# Connectors.net
KiCad netlist of a schematic drawn in Altium Designer
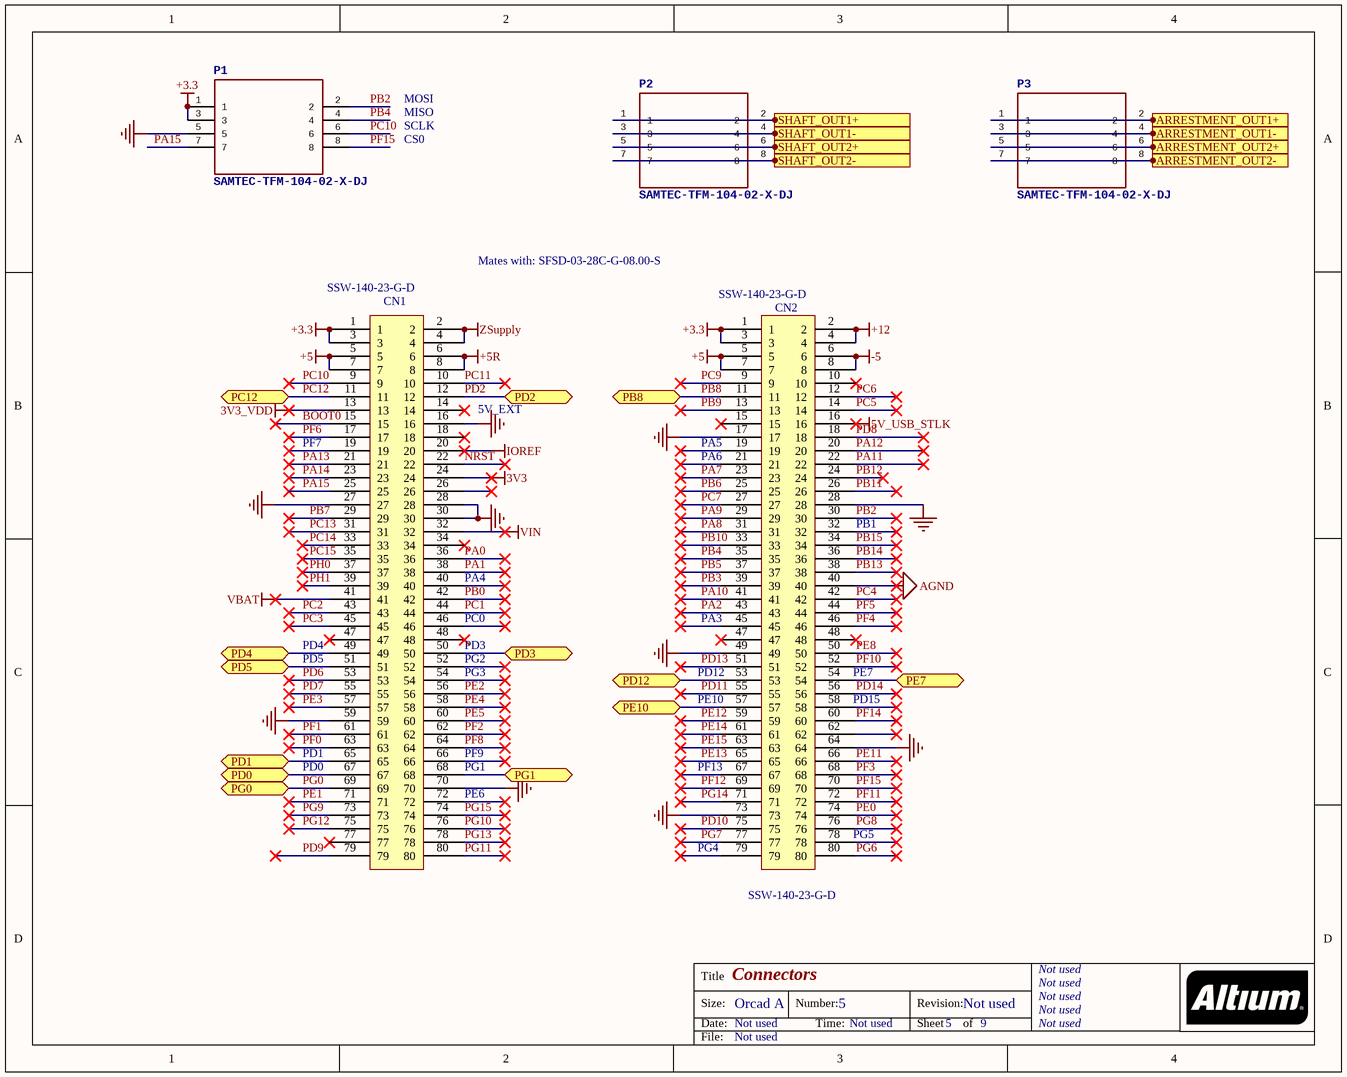
[diagram p0: Connectors.SchDoc]

(export (version "E")
  (design (tool "Eeschema 10.0.6"))
  (components
    (comp (ref "CN1")
      (value "SSW-140-23-G-D")
      (footprint "SSW-140-23-G-D")
      (description "80 Position Receptacle Connector Through Hole")
      (fields (field (name "SUPPLIER PART NUMBER 1") "SSW-140-23-G-D") (field (name "MANUFACTURER") "Samtec"))
      (libsource (lib "ZLS_Schematic_lib") (part "SSW-140-23-G-D"))
    )
    (comp (ref "CN2")
      (value "SSW-140-23-G-D")
      (footprint "SSW-140-23-G-D")
      (description "80 Position Receptacle Connector Through Hole")
      (fields (field (name "SUPPLIER PART NUMBER 1") "SSW-140-23-G-D") (field (name "MANUFACTURER") "Samtec"))
      (libsource (lib "ZLS_Schematic_lib") (part "SSW-140-23-G-D"))
    )
    (comp (ref "P1")
      (value "SAMTEC-TFM-104-02-X-DJ")
      (footprint "SAMTEC-TFM-104-02-X-D")
      (libsource (lib "SAMTEC-TFM-104-02-X-D") (part "SAMTEC-TFM-104-02-X-DJ"))
    )
    (comp (ref "P2")
      (value "SAMTEC-TFM-104-02-X-DJ")
      (footprint "SAMTEC-TFM-104-02-X-D")
      (libsource (lib "SAMTEC-TFM-104-02-X-D") (part "SAMTEC-TFM-104-02-X-DJ"))
    )
    (comp (ref "P3")
      (value "SAMTEC-TFM-104-02-X-DJ")
      (footprint "SAMTEC-TFM-104-02-X-D")
      (libsource (lib "SAMTEC-TFM-104-02-X-D") (part "SAMTEC-TFM-104-02-X-DJ"))
    )
  )
  (nets
    (net (code "1") (name "+3.3") (class "Default")
      (node (ref "CN1") (pin "1") (pinfunction "1_1") (pintype "passive"))
      (node (ref "CN1") (pin "3") (pinfunction "3_3") (pintype "passive"))
      (node (ref "CN2") (pin "1") (pinfunction "1_1") (pintype "passive"))
      (node (ref "CN2") (pin "3") (pinfunction "3_3") (pintype "passive"))
      (node (ref "P1") (pin "1") (pinfunction "1_1") (pintype "passive"))
      (node (ref "P1") (pin "3") (pinfunction "3_3") (pintype "passive"))
    )
    (net (code "2") (name "+5") (class "Default")
      (node (ref "CN1") (pin "5") (pinfunction "5_5") (pintype "passive"))
      (node (ref "CN1") (pin "7") (pinfunction "7_7") (pintype "passive"))
      (node (ref "CN2") (pin "5") (pinfunction "5_5") (pintype "passive"))
      (node (ref "CN2") (pin "7") (pinfunction "7_7") (pintype "passive"))
    )
    (net (code "3") (name "+5R") (class "Default")
      (node (ref "CN1") (pin "6") (pinfunction "6_6") (pintype "passive"))
      (node (ref "CN1") (pin "8") (pinfunction "8_8") (pintype "passive"))
    )
    (net (code "4") (name "+12") (class "Default")
      (node (ref "CN2") (pin "2") (pinfunction "2_2") (pintype "passive"))
      (node (ref "CN2") (pin "4") (pinfunction "4_4") (pintype "passive"))
    )
    (net (code "5") (name "-5") (class "Default")
      (node (ref "CN2") (pin "6") (pinfunction "6_6") (pintype "passive"))
      (node (ref "CN2") (pin "8") (pinfunction "8_8") (pintype "passive"))
    )
    (net (code "6") (name "/ARRESTMENT_OUT1+") (class "Default")
      (node (ref "P3") (pin "1") (pinfunction "1_1") (pintype "passive"))
      (node (ref "P3") (pin "2") (pinfunction "2_2") (pintype "passive"))
    )
    (net (code "7") (name "/ARRESTMENT_OUT1-") (class "Default")
      (node (ref "P3") (pin "3") (pinfunction "3_3") (pintype "passive"))
      (node (ref "P3") (pin "4") (pinfunction "4_4") (pintype "passive"))
    )
    (net (code "8") (name "/ARRESTMENT_OUT2+") (class "Default")
      (node (ref "P3") (pin "5") (pinfunction "5_5") (pintype "passive"))
      (node (ref "P3") (pin "6") (pinfunction "6_6") (pintype "passive"))
    )
    (net (code "9") (name "/ARRESTMENT_OUT2-") (class "Default")
      (node (ref "P3") (pin "7") (pinfunction "7_7") (pintype "passive"))
      (node (ref "P3") (pin "8") (pinfunction "8_8") (pintype "passive"))
    )
    (net (code "10") (name "/BOOT0") (class "Default")
      (node (ref "CN1") (pin "15") (pinfunction "15_15") (pintype "passive+no_connect"))
    )
    (net (code "11") (name "/NRST") (class "Default")
      (node (ref "CN1") (pin "22") (pinfunction "22_22") (pintype "passive+no_connect"))
    )
    (net (code "12") (name "/PA0") (class "Default")
      (node (ref "CN1") (pin "36") (pinfunction "36_36") (pintype "passive+no_connect"))
    )
    (net (code "13") (name "/PA1") (class "Default")
      (node (ref "CN1") (pin "38") (pinfunction "38_38") (pintype "passive+no_connect"))
    )
    (net (code "14") (name "/PA2") (class "Default")
      (node (ref "CN2") (pin "43") (pinfunction "43_43") (pintype "passive+no_connect"))
    )
    (net (code "15") (name "/PA7") (class "Default")
      (node (ref "CN2") (pin "23") (pinfunction "23_23") (pintype "passive+no_connect"))
    )
    (net (code "16") (name "/PA8") (class "Default")
      (node (ref "CN2") (pin "31") (pinfunction "31_31") (pintype "passive+no_connect"))
    )
    (net (code "17") (name "/PA9") (class "Default")
      (node (ref "CN2") (pin "29") (pinfunction "29_29") (pintype "passive+no_connect"))
    )
    (net (code "18") (name "/PA10") (class "Default")
      (node (ref "CN2") (pin "41") (pinfunction "41_41") (pintype "passive+no_connect"))
    )
    (net (code "19") (name "/PA11") (class "Default")
      (node (ref "CN2") (pin "22") (pinfunction "22_22") (pintype "passive+no_connect"))
    )
    (net (code "20") (name "/PA12") (class "Default")
      (node (ref "CN2") (pin "20") (pinfunction "20_20") (pintype "passive+no_connect"))
    )
    (net (code "21") (name "/PA13") (class "Default")
      (node (ref "CN1") (pin "21") (pinfunction "21_21") (pintype "passive+no_connect"))
    )
    (net (code "22") (name "/PA14") (class "Default")
      (node (ref "CN1") (pin "23") (pinfunction "23_23") (pintype "passive+no_connect"))
    )
    (net (code "23") (name "/PA15") (class "Default")
      (node (ref "CN1") (pin "25") (pinfunction "25_25") (pintype "passive"))
      (node (ref "P1") (pin "7") (pinfunction "7_7") (pintype "passive"))
    )
    (net (code "24") (name "/PB0") (class "Default")
      (node (ref "CN1") (pin "42") (pinfunction "42_42") (pintype "passive+no_connect"))
    )
    (net (code "25") (name "/PB2") (class "Default")
      (node (ref "CN2") (pin "30") (pinfunction "30_30") (pintype "passive"))
      (node (ref "P1") (pin "2") (pinfunction "2_2") (pintype "passive"))
    )
    (net (code "26") (name "/PB3") (class "Default")
      (node (ref "CN2") (pin "39") (pinfunction "39_39") (pintype "passive+no_connect"))
    )
    (net (code "27") (name "/PB4") (class "Default")
      (node (ref "CN2") (pin "35") (pinfunction "35_35") (pintype "passive"))
      (node (ref "P1") (pin "4") (pinfunction "4_4") (pintype "passive"))
    )
    (net (code "28") (name "/PB5") (class "Default")
      (node (ref "CN2") (pin "37") (pinfunction "37_37") (pintype "passive+no_connect"))
    )
    (net (code "29") (name "/PB6") (class "Default")
      (node (ref "CN2") (pin "25") (pinfunction "25_25") (pintype "passive+no_connect"))
    )
    (net (code "30") (name "/PB7") (class "Default")
      (node (ref "CN1") (pin "29") (pinfunction "29_29") (pintype "passive+no_connect"))
    )
    (net (code "31") (name "/PB8") (class "Default")
      (node (ref "CN2") (pin "11") (pinfunction "11_11") (pintype "passive"))
    )
    (net (code "32") (name "/PB9") (class "Default")
      (node (ref "CN2") (pin "13") (pinfunction "13_13") (pintype "passive+no_connect"))
    )
    (net (code "33") (name "/PB10") (class "Default")
      (node (ref "CN2") (pin "33") (pinfunction "33_33") (pintype "passive+no_connect"))
    )
    (net (code "34") (name "/PB11") (class "Default")
      (node (ref "CN2") (pin "26") (pinfunction "26_26") (pintype "passive+no_connect"))
    )
    (net (code "35") (name "/PB12") (class "Default")
      (node (ref "CN2") (pin "24") (pinfunction "24_24") (pintype "passive+no_connect"))
    )
    (net (code "36") (name "/PB13") (class "Default")
      (node (ref "CN2") (pin "38") (pinfunction "38_38") (pintype "passive+no_connect"))
    )
    (net (code "37") (name "/PB14") (class "Default")
      (node (ref "CN2") (pin "36") (pinfunction "36_36") (pintype "passive+no_connect"))
    )
    (net (code "38") (name "/PB15") (class "Default")
      (node (ref "CN2") (pin "34") (pinfunction "34_34") (pintype "passive+no_connect"))
    )
    (net (code "39") (name "/PC1") (class "Default")
      (node (ref "CN1") (pin "44") (pinfunction "44_44") (pintype "passive+no_connect"))
    )
    (net (code "40") (name "/PC2") (class "Default")
      (node (ref "CN1") (pin "43") (pinfunction "43_43") (pintype "passive+no_connect"))
    )
    (net (code "41") (name "/PC3") (class "Default")
      (node (ref "CN1") (pin "45") (pinfunction "45_45") (pintype "passive+no_connect"))
    )
    (net (code "42") (name "/PC4") (class "Default")
      (node (ref "CN2") (pin "42") (pinfunction "42_42") (pintype "passive+no_connect"))
    )
    (net (code "43") (name "/PC5") (class "Default")
      (node (ref "CN2") (pin "14") (pinfunction "14_14") (pintype "passive+no_connect"))
    )
    (net (code "44") (name "/PC6") (class "Default")
      (node (ref "CN2") (pin "12") (pinfunction "12_12") (pintype "passive+no_connect"))
    )
    (net (code "45") (name "/PC7") (class "Default")
      (node (ref "CN2") (pin "27") (pinfunction "27_27") (pintype "passive+no_connect"))
    )
    (net (code "46") (name "/PC9") (class "Default")
      (node (ref "CN2") (pin "9") (pinfunction "9_9") (pintype "passive+no_connect"))
    )
    (net (code "47") (name "/PC10") (class "Default")
      (node (ref "CN1") (pin "9") (pinfunction "9_9") (pintype "passive"))
      (node (ref "P1") (pin "6") (pinfunction "6_6") (pintype "passive"))
    )
    (net (code "48") (name "/PC11") (class "Default")
      (node (ref "CN1") (pin "10") (pinfunction "10_10") (pintype "passive+no_connect"))
    )
    (net (code "49") (name "/PC12") (class "Default")
      (node (ref "CN1") (pin "11") (pinfunction "11_11") (pintype "passive"))
    )
    (net (code "50") (name "/PC13") (class "Default")
      (node (ref "CN1") (pin "31") (pinfunction "31_31") (pintype "passive+no_connect"))
    )
    (net (code "51") (name "/PC14") (class "Default")
      (node (ref "CN1") (pin "33") (pinfunction "33_33") (pintype "passive+no_connect"))
    )
    (net (code "52") (name "/PC15") (class "Default")
      (node (ref "CN1") (pin "35") (pinfunction "35_35") (pintype "passive+no_connect"))
    )
    (net (code "53") (name "/PD0") (class "Default")
      (node (ref "CN1") (pin "67") (pinfunction "67_67") (pintype "passive"))
    )
    (net (code "54") (name "/PD1") (class "Default")
      (node (ref "CN1") (pin "65") (pinfunction "65_65") (pintype "passive"))
    )
    (net (code "55") (name "/PD2") (class "Default")
      (node (ref "CN1") (pin "12") (pinfunction "12_12") (pintype "passive"))
    )
    (net (code "56") (name "/PD3") (class "Default")
      (node (ref "CN1") (pin "50") (pinfunction "50_50") (pintype "passive"))
    )
    (net (code "57") (name "/PD4") (class "Default")
      (node (ref "CN1") (pin "49") (pinfunction "49_49") (pintype "passive"))
    )
    (net (code "58") (name "/PD5") (class "Default")
      (node (ref "CN1") (pin "51") (pinfunction "51_51") (pintype "passive"))
    )
    (net (code "59") (name "/PD6") (class "Default")
      (node (ref "CN1") (pin "53") (pinfunction "53_53") (pintype "passive+no_connect"))
    )
    (net (code "60") (name "/PD7") (class "Default")
      (node (ref "CN1") (pin "55") (pinfunction "55_55") (pintype "passive+no_connect"))
    )
    (net (code "61") (name "/PD8") (class "Default")
      (node (ref "CN2") (pin "18") (pinfunction "18_18") (pintype "passive+no_connect"))
    )
    (net (code "62") (name "/PD9") (class "Default")
      (node (ref "CN1") (pin "79") (pinfunction "79_79") (pintype "passive+no_connect"))
    )
    (net (code "63") (name "/PD10") (class "Default")
      (node (ref "CN2") (pin "75") (pinfunction "75_75") (pintype "passive+no_connect"))
    )
    (net (code "64") (name "/PD11") (class "Default")
      (node (ref "CN2") (pin "55") (pinfunction "55_55") (pintype "passive+no_connect"))
    )
    (net (code "65") (name "/PD12") (class "Default")
      (node (ref "CN2") (pin "53") (pinfunction "53_53") (pintype "passive"))
    )
    (net (code "66") (name "/PD13") (class "Default")
      (node (ref "CN2") (pin "51") (pinfunction "51_51") (pintype "passive+no_connect"))
    )
    (net (code "67") (name "/PD14") (class "Default")
      (node (ref "CN2") (pin "56") (pinfunction "56_56") (pintype "passive+no_connect"))
    )
    (net (code "68") (name "/PE0") (class "Default")
      (node (ref "CN2") (pin "74") (pinfunction "74_74") (pintype "passive+no_connect"))
    )
    (net (code "69") (name "/PE1") (class "Default")
      (node (ref "CN1") (pin "71") (pinfunction "71_71") (pintype "passive+no_connect"))
    )
    (net (code "70") (name "/PE2") (class "Default")
      (node (ref "CN1") (pin "56") (pinfunction "56_56") (pintype "passive+no_connect"))
    )
    (net (code "71") (name "/PE3") (class "Default")
      (node (ref "CN1") (pin "57") (pinfunction "57_57") (pintype "passive+no_connect"))
    )
    (net (code "72") (name "/PE4") (class "Default")
      (node (ref "CN1") (pin "58") (pinfunction "58_58") (pintype "passive+no_connect"))
    )
    (net (code "73") (name "/PE5") (class "Default")
      (node (ref "CN1") (pin "60") (pinfunction "60_60") (pintype "passive+no_connect"))
    )
    (net (code "74") (name "/PE7") (class "Default")
      (node (ref "CN2") (pin "54") (pinfunction "54_54") (pintype "passive"))
    )
    (net (code "75") (name "/PE8") (class "Default")
      (node (ref "CN2") (pin "50") (pinfunction "50_50") (pintype "passive+no_connect"))
    )
    (net (code "76") (name "/PE10") (class "Default")
      (node (ref "CN2") (pin "57") (pinfunction "57_57") (pintype "passive"))
    )
    (net (code "77") (name "/PE11") (class "Default")
      (node (ref "CN2") (pin "66") (pinfunction "66_66") (pintype "passive+no_connect"))
    )
    (net (code "78") (name "/PE12") (class "Default")
      (node (ref "CN2") (pin "59") (pinfunction "59_59") (pintype "passive+no_connect"))
    )
    (net (code "79") (name "/PE13") (class "Default")
      (node (ref "CN2") (pin "65") (pinfunction "65_65") (pintype "passive+no_connect"))
    )
    (net (code "80") (name "/PE14") (class "Default")
      (node (ref "CN2") (pin "61") (pinfunction "61_61") (pintype "passive+no_connect"))
    )
    (net (code "81") (name "/PE15") (class "Default")
      (node (ref "CN2") (pin "63") (pinfunction "63_63") (pintype "passive+no_connect"))
    )
    (net (code "82") (name "/PF0") (class "Default")
      (node (ref "CN1") (pin "63") (pinfunction "63_63") (pintype "passive+no_connect"))
    )
    (net (code "83") (name "/PF1") (class "Default")
      (node (ref "CN1") (pin "61") (pinfunction "61_61") (pintype "passive+no_connect"))
    )
    (net (code "84") (name "/PF2") (class "Default")
      (node (ref "CN1") (pin "62") (pinfunction "62_62") (pintype "passive+no_connect"))
    )
    (net (code "85") (name "/PF3") (class "Default")
      (node (ref "CN2") (pin "68") (pinfunction "68_68") (pintype "passive+no_connect"))
    )
    (net (code "86") (name "/PF4") (class "Default")
      (node (ref "CN2") (pin "46") (pinfunction "46_46") (pintype "passive+no_connect"))
    )
    (net (code "87") (name "/PF5") (class "Default")
      (node (ref "CN2") (pin "44") (pinfunction "44_44") (pintype "passive+no_connect"))
    )
    (net (code "88") (name "/PF6") (class "Default")
      (node (ref "CN1") (pin "17") (pinfunction "17_17") (pintype "passive+no_connect"))
    )
    (net (code "89") (name "/PF8") (class "Default")
      (node (ref "CN1") (pin "64") (pinfunction "64_64") (pintype "passive+no_connect"))
    )
    (net (code "90") (name "/PF10") (class "Default")
      (node (ref "CN2") (pin "52") (pinfunction "52_52") (pintype "passive+no_connect"))
    )
    (net (code "91") (name "/PF11") (class "Default")
      (node (ref "CN2") (pin "72") (pinfunction "72_72") (pintype "passive+no_connect"))
    )
    (net (code "92") (name "/PF12") (class "Default")
      (node (ref "CN2") (pin "69") (pinfunction "69_69") (pintype "passive+no_connect"))
    )
    (net (code "93") (name "/PF14") (class "Default")
      (node (ref "CN2") (pin "60") (pinfunction "60_60") (pintype "passive+no_connect"))
    )
    (net (code "94") (name "/PF15") (class "Default")
      (node (ref "CN2") (pin "70") (pinfunction "70_70") (pintype "passive"))
      (node (ref "P1") (pin "8") (pinfunction "8_8") (pintype "passive"))
    )
    (net (code "95") (name "/PG0") (class "Default")
      (node (ref "CN1") (pin "69") (pinfunction "69_69") (pintype "passive"))
    )
    (net (code "96") (name "/PG1") (class "Default")
      (node (ref "CN1") (pin "68") (pinfunction "68_68") (pintype "passive"))
    )
    (net (code "97") (name "/PG6") (class "Default")
      (node (ref "CN2") (pin "80") (pinfunction "80_80") (pintype "passive+no_connect"))
    )
    (net (code "98") (name "/PG7") (class "Default")
      (node (ref "CN2") (pin "77") (pinfunction "77_77") (pintype "passive+no_connect"))
    )
    (net (code "99") (name "/PG8") (class "Default")
      (node (ref "CN2") (pin "76") (pinfunction "76_76") (pintype "passive+no_connect"))
    )
    (net (code "100") (name "/PG9") (class "Default")
      (node (ref "CN1") (pin "73") (pinfunction "73_73") (pintype "passive+no_connect"))
    )
    (net (code "101") (name "/PG10") (class "Default")
      (node (ref "CN1") (pin "76") (pinfunction "76_76") (pintype "passive+no_connect"))
    )
    (net (code "102") (name "/PG11") (class "Default")
      (node (ref "CN1") (pin "80") (pinfunction "80_80") (pintype "passive+no_connect"))
    )
    (net (code "103") (name "/PG12") (class "Default")
      (node (ref "CN1") (pin "75") (pinfunction "75_75") (pintype "passive+no_connect"))
    )
    (net (code "104") (name "/PG13") (class "Default")
      (node (ref "CN1") (pin "78") (pinfunction "78_78") (pintype "passive+no_connect"))
    )
    (net (code "105") (name "/PG14") (class "Default")
      (node (ref "CN2") (pin "71") (pinfunction "71_71") (pintype "passive+no_connect"))
    )
    (net (code "106") (name "/PG15") (class "Default")
      (node (ref "CN1") (pin "74") (pinfunction "74_74") (pintype "passive+no_connect"))
    )
    (net (code "107") (name "/PH0") (class "Default")
      (node (ref "CN1") (pin "37") (pinfunction "37_37") (pintype "passive+no_connect"))
    )
    (net (code "108") (name "/PH1") (class "Default")
      (node (ref "CN1") (pin "39") (pinfunction "39_39") (pintype "passive+no_connect"))
    )
    (net (code "109") (name "/SHAFT_OUT1+") (class "Default")
      (node (ref "P2") (pin "1") (pinfunction "1_1") (pintype "passive"))
      (node (ref "P2") (pin "2") (pinfunction "2_2") (pintype "passive"))
    )
    (net (code "110") (name "/SHAFT_OUT1-") (class "Default")
      (node (ref "P2") (pin "3") (pinfunction "3_3") (pintype "passive"))
      (node (ref "P2") (pin "4") (pinfunction "4_4") (pintype "passive"))
    )
    (net (code "111") (name "/SHAFT_OUT2+") (class "Default")
      (node (ref "P2") (pin "5") (pinfunction "5_5") (pintype "passive"))
      (node (ref "P2") (pin "6") (pinfunction "6_6") (pintype "passive"))
    )
    (net (code "112") (name "/SHAFT_OUT2-") (class "Default")
      (node (ref "P2") (pin "7") (pinfunction "7_7") (pintype "passive"))
      (node (ref "P2") (pin "8") (pinfunction "8_8") (pintype "passive"))
    )
    (net (code "113") (name "3V3") (class "Default")
      (node (ref "CN1") (pin "24") (pinfunction "24_24") (pintype "passive"))
    )
    (net (code "114") (name "3V3_VDD") (class "Default")
      (node (ref "CN1") (pin "13") (pinfunction "13_13") (pintype "passive"))
    )
    (net (code "115") (name "5V_USB_STLK") (class "Default")
      (node (ref "CN2") (pin "16") (pinfunction "16_16") (pintype "passive"))
    )
    (net (code "116") (name "AGND") (class "Default")
      (node (ref "CN2") (pin "40") (pinfunction "40_40") (pintype "passive"))
    )
    (net (code "117") (name "GND") (class "Default")
      (node (ref "CN1") (pin "16") (pinfunction "16_16") (pintype "passive"))
      (node (ref "CN1") (pin "27") (pinfunction "27_27") (pintype "passive"))
      (node (ref "CN1") (pin "28") (pinfunction "28_28") (pintype "passive"))
      (node (ref "CN1") (pin "30") (pinfunction "30_30") (pintype "passive"))
      (node (ref "CN1") (pin "59") (pinfunction "59_59") (pintype "passive"))
      (node (ref "CN1") (pin "70") (pinfunction "70_70") (pintype "passive"))
      (node (ref "CN2") (pin "17") (pinfunction "17_17") (pintype "passive"))
      (node (ref "CN2") (pin "28") (pinfunction "28_28") (pintype "passive"))
      (node (ref "CN2") (pin "49") (pinfunction "49_49") (pintype "passive"))
      (node (ref "CN2") (pin "64") (pinfunction "64_64") (pintype "passive"))
      (node (ref "CN2") (pin "73") (pinfunction "73_73") (pintype "passive"))
      (node (ref "P1") (pin "5") (pinfunction "5_5") (pintype "passive"))
    )
    (net (code "118") (name "IOREF") (class "Default")
      (node (ref "CN1") (pin "20") (pinfunction "20_20") (pintype "passive"))
    )
    (net (code "119") (name "VBAT") (class "Default")
      (node (ref "CN1") (pin "41") (pinfunction "41_41") (pintype "passive"))
    )
    (net (code "120") (name "VIN") (class "Default")
      (node (ref "CN1") (pin "32") (pinfunction "32_32") (pintype "passive"))
    )
    (net (code "121") (name "ZSupply") (class "Default")
      (node (ref "CN1") (pin "2") (pinfunction "2_2") (pintype "passive"))
      (node (ref "CN1") (pin "4") (pinfunction "4_4") (pintype "passive"))
    )
    (net (code "122") (name "unconnected-(CN1-Pad14)") (class "Default")
      (node (ref "CN1") (pin "14") (pinfunction "14_14") (pintype "passive+no_connect"))
    )
    (net (code "123") (name "unconnected-(CN1-Pad18)") (class "Default")
      (node (ref "CN1") (pin "18") (pinfunction "18_18") (pintype "passive+no_connect"))
    )
    (net (code "124") (name "unconnected-(CN1-Pad19)") (class "Default")
      (node (ref "CN1") (pin "19") (pinfunction "19_19") (pintype "passive+no_connect"))
    )
    (net (code "125") (name "unconnected-(CN1-Pad26)") (class "Default")
      (node (ref "CN1") (pin "26") (pinfunction "26_26") (pintype "passive+no_connect"))
    )
    (net (code "126") (name "unconnected-(CN1-Pad34)") (class "Default")
      (node (ref "CN1") (pin "34") (pinfunction "34_34") (pintype "passive+no_connect"))
    )
    (net (code "127") (name "unconnected-(CN1-Pad40)") (class "Default")
      (node (ref "CN1") (pin "40") (pinfunction "40_40") (pintype "passive+no_connect"))
    )
    (net (code "128") (name "unconnected-(CN1-Pad46)") (class "Default")
      (node (ref "CN1") (pin "46") (pinfunction "46_46") (pintype "passive+no_connect"))
    )
    (net (code "129") (name "unconnected-(CN1-Pad47)") (class "Default")
      (node (ref "CN1") (pin "47") (pinfunction "47_47") (pintype "passive+no_connect"))
    )
    (net (code "130") (name "unconnected-(CN1-Pad48)") (class "Default")
      (node (ref "CN1") (pin "48") (pinfunction "48_48") (pintype "passive+no_connect"))
    )
    (net (code "131") (name "unconnected-(CN1-Pad52)") (class "Default")
      (node (ref "CN1") (pin "52") (pinfunction "52_52") (pintype "passive+no_connect"))
    )
    (net (code "132") (name "unconnected-(CN1-Pad54)") (class "Default")
      (node (ref "CN1") (pin "54") (pinfunction "54_54") (pintype "passive+no_connect"))
    )
    (net (code "133") (name "unconnected-(CN1-Pad66)") (class "Default")
      (node (ref "CN1") (pin "66") (pinfunction "66_66") (pintype "passive+no_connect"))
    )
    (net (code "134") (name "unconnected-(CN1-Pad72)") (class "Default")
      (node (ref "CN1") (pin "72") (pinfunction "72_72") (pintype "passive+no_connect"))
    )
    (net (code "135") (name "unconnected-(CN1-Pad77)") (class "Default")
      (node (ref "CN1") (pin "77") (pinfunction "77_77") (pintype "passive+no_connect"))
    )
    (net (code "136") (name "unconnected-(CN2-Pad10)") (class "Default")
      (node (ref "CN2") (pin "10") (pinfunction "10_10") (pintype "passive+no_connect"))
    )
    (net (code "137") (name "unconnected-(CN2-Pad15)") (class "Default")
      (node (ref "CN2") (pin "15") (pinfunction "15_15") (pintype "passive+no_connect"))
    )
    (net (code "138") (name "unconnected-(CN2-Pad19)") (class "Default")
      (node (ref "CN2") (pin "19") (pinfunction "19_19") (pintype "passive+no_connect"))
    )
    (net (code "139") (name "unconnected-(CN2-Pad21)") (class "Default")
      (node (ref "CN2") (pin "21") (pinfunction "21_21") (pintype "passive+no_connect"))
    )
    (net (code "140") (name "unconnected-(CN2-Pad32)") (class "Default")
      (node (ref "CN2") (pin "32") (pinfunction "32_32") (pintype "passive+no_connect"))
    )
    (net (code "141") (name "unconnected-(CN2-Pad45)") (class "Default")
      (node (ref "CN2") (pin "45") (pinfunction "45_45") (pintype "passive+no_connect"))
    )
    (net (code "142") (name "unconnected-(CN2-Pad47)") (class "Default")
      (node (ref "CN2") (pin "47") (pinfunction "47_47") (pintype "passive+no_connect"))
    )
    (net (code "143") (name "unconnected-(CN2-Pad48)") (class "Default")
      (node (ref "CN2") (pin "48") (pinfunction "48_48") (pintype "passive+no_connect"))
    )
    (net (code "144") (name "unconnected-(CN2-Pad58)") (class "Default")
      (node (ref "CN2") (pin "58") (pinfunction "58_58") (pintype "passive+no_connect"))
    )
    (net (code "145") (name "unconnected-(CN2-Pad62)") (class "Default")
      (node (ref "CN2") (pin "62") (pinfunction "62_62") (pintype "passive+no_connect"))
    )
    (net (code "146") (name "unconnected-(CN2-Pad67)") (class "Default")
      (node (ref "CN2") (pin "67") (pinfunction "67_67") (pintype "passive+no_connect"))
    )
    (net (code "147") (name "unconnected-(CN2-Pad78)") (class "Default")
      (node (ref "CN2") (pin "78") (pinfunction "78_78") (pintype "passive+no_connect"))
    )
    (net (code "148") (name "unconnected-(CN2-Pad79)") (class "Default")
      (node (ref "CN2") (pin "79") (pinfunction "79_79") (pintype "passive+no_connect"))
    )
  )
)
